# Sheet_4.net
KiCad netlist of a schematic drawn in Altium Designer
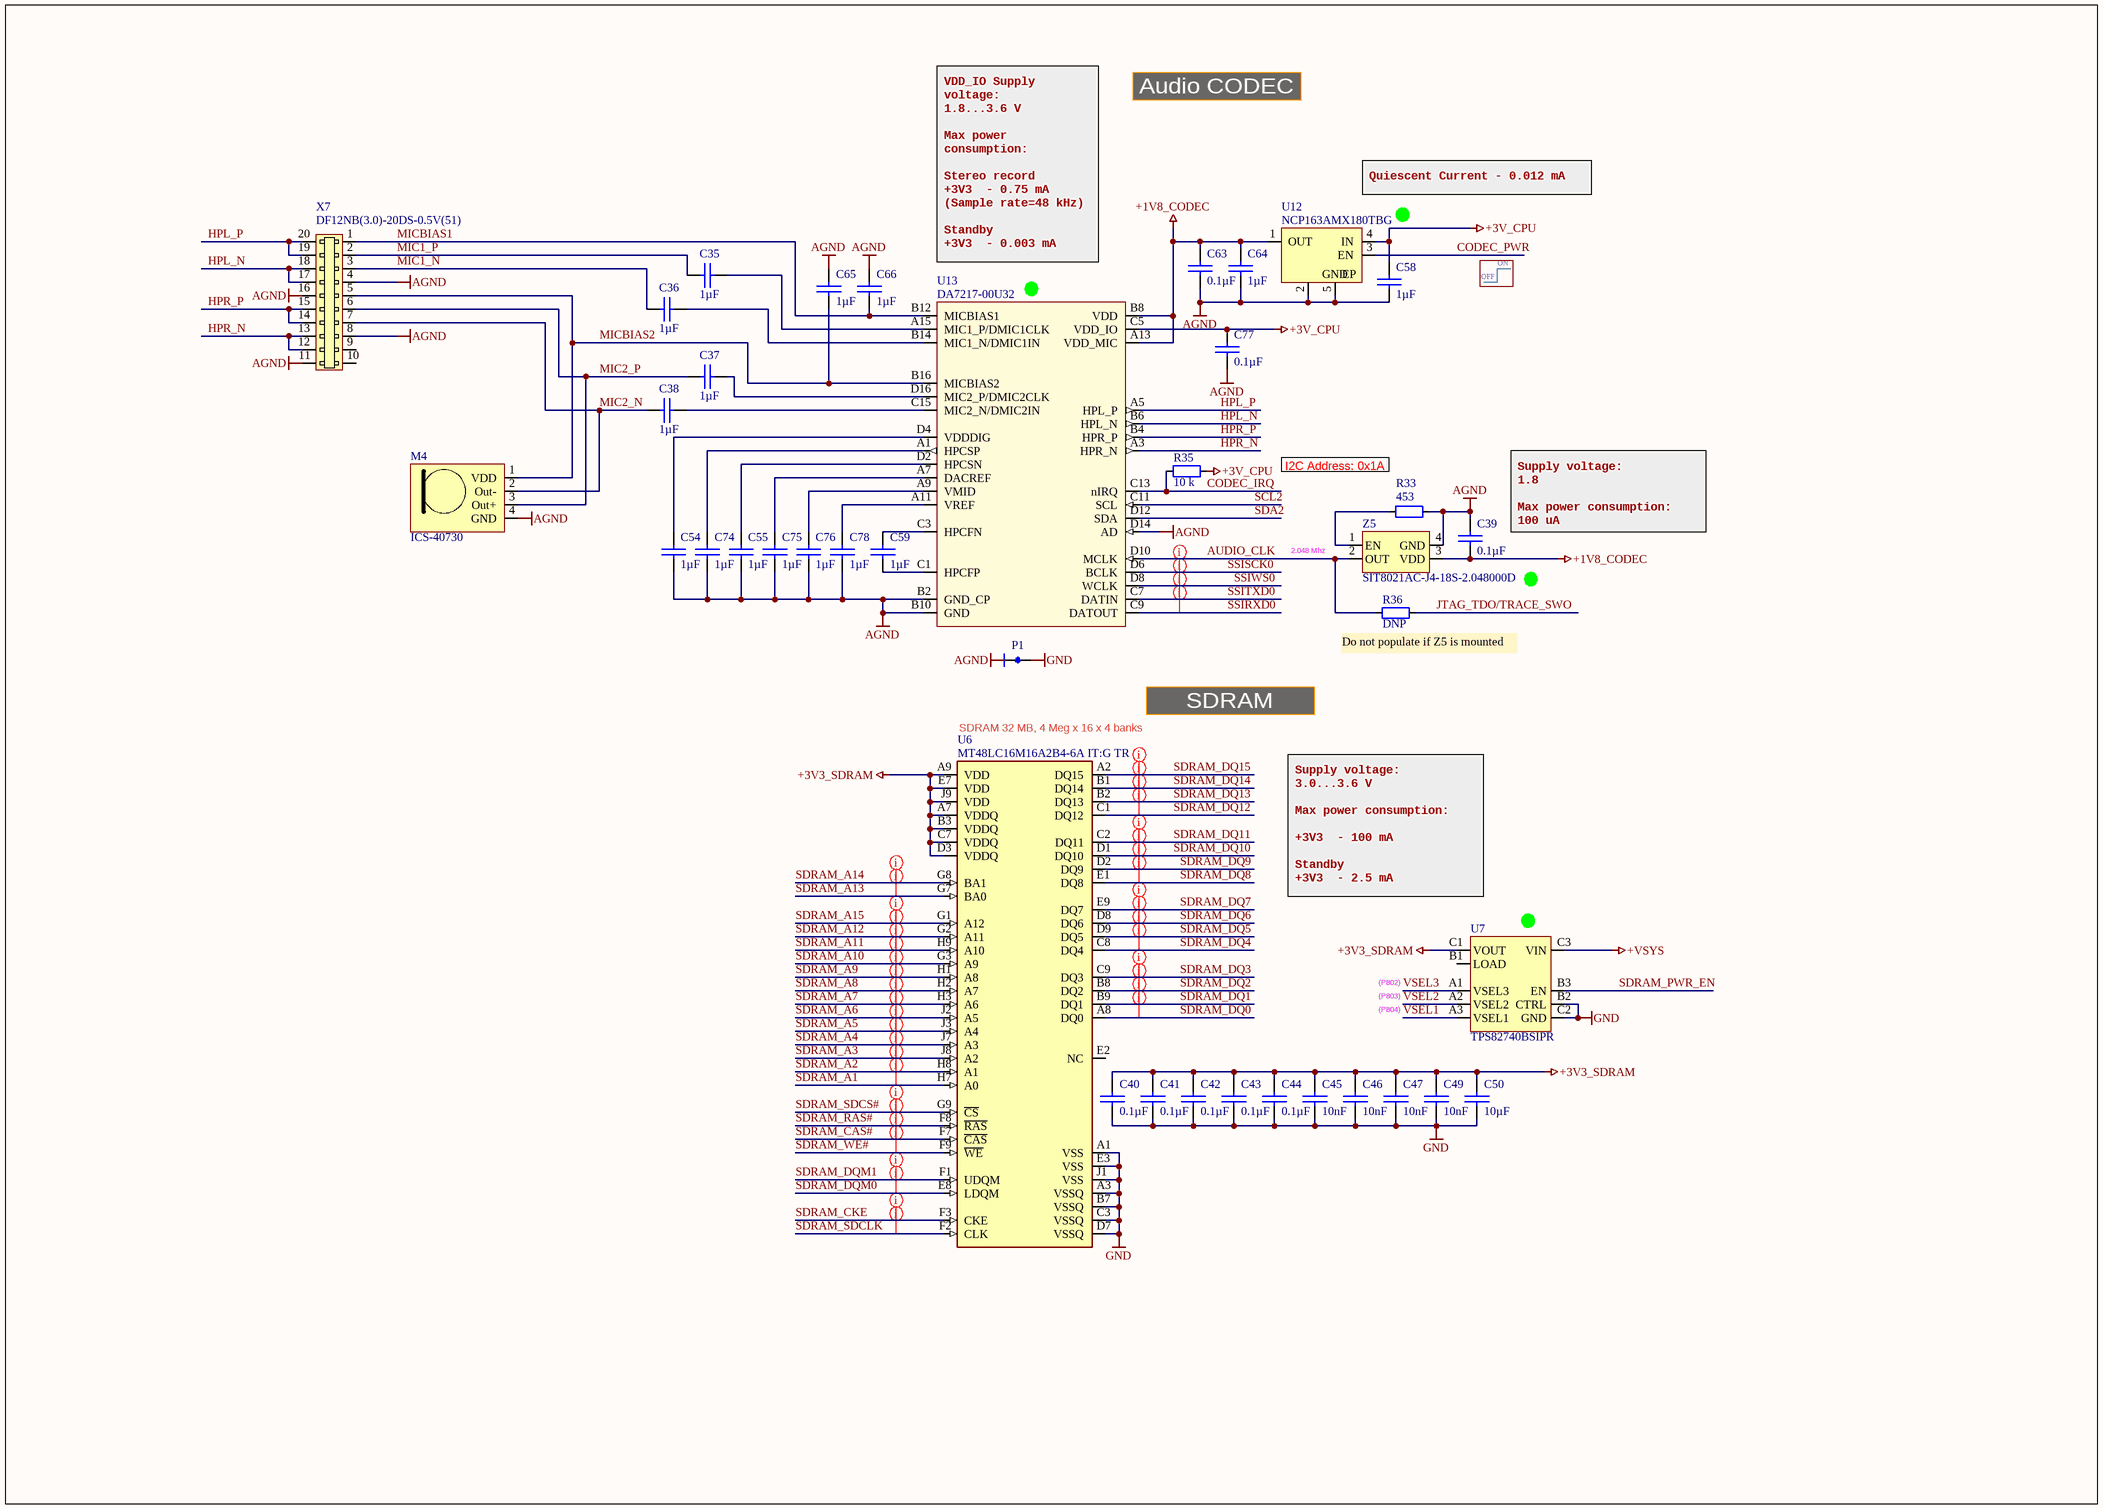
[diagram p0: Sheet_4.SchDoc]

(export (version "E")
  (design (tool "Eeschema 10.0.6"))
  (components
    (comp (ref "C35")
      (value "1µF")
      (footprint "0402 CAP")
      (description "1µF, ±20%, 25V, X5R, 0402 (1005 Metric), -55°C ~ 85°C, -, General Purpose")
      (fields (field (name "PART NUMBER") "TMK105BJ105MV-F") (field (name "MANUFACTURER") "Taiyo Yuden"))
      (libsource (lib "ea_PassivComps") (part "Capacitor"))
    )
    (comp (ref "C36")
      (value "1µF")
      (footprint "0402 CAP")
      (description "1µF, ±20%, 25V, X5R, 0402 (1005 Metric), -55°C ~ 85°C, -, General Purpose")
      (fields (field (name "PART NUMBER") "TMK105BJ105MV-F") (field (name "MANUFACTURER") "Taiyo Yuden"))
      (libsource (lib "ea_PassivComps") (part "Capacitor"))
    )
    (comp (ref "C37")
      (value "1µF")
      (footprint "0402 CAP")
      (description "1µF, ±20%, 25V, X5R, 0402 (1005 Metric), -55°C ~ 85°C, -, General Purpose")
      (fields (field (name "PART NUMBER") "TMK105BJ105MV-F") (field (name "MANUFACTURER") "Taiyo Yuden"))
      (libsource (lib "ea_PassivComps") (part "Capacitor"))
    )
    (comp (ref "C38")
      (value "1µF")
      (footprint "0402 CAP")
      (description "1µF, ±20%, 25V, X5R, 0402 (1005 Metric), -55°C ~ 85°C, -, General Purpose")
      (fields (field (name "PART NUMBER") "TMK105BJ105MV-F") (field (name "MANUFACTURER") "Taiyo Yuden"))
      (libsource (lib "ea_PassivComps") (part "Capacitor"))
    )
    (comp (ref "C39")
      (value "0.1µF")
      (footprint "0402 CAP")
      (description "0.1µF, ±10%, 50V, X7R, 0402 (1005 Metric), -55°C ~ 125°C, -, General Purpose")
      (fields
        (field (name "PART NUMBER") "0402B104K500CT")
        (field (name "MANUFACTURER") "Walsin Technology Corporation")
      )
      (libsource (lib "ea_PassivComps") (part "Capacitor"))
    )
    (comp (ref "C40")
      (value "0.1µF")
      (footprint "0402 CAP")
      (description "0.1µF, ±10%, 50V, X7R, 0402 (1005 Metric), -55°C ~ 125°C, -, General Purpose")
      (fields
        (field (name "PART NUMBER") "0402B104K500CT")
        (field (name "MANUFACTURER") "Walsin Technology Corporation")
      )
      (libsource (lib "ea_PassivComps") (part "Capacitor"))
    )
    (comp (ref "C41")
      (value "0.1µF")
      (footprint "0402 CAP")
      (description "0.1µF, ±10%, 50V, X7R, 0402 (1005 Metric), -55°C ~ 125°C, -, General Purpose")
      (fields
        (field (name "PART NUMBER") "0402B104K500CT")
        (field (name "MANUFACTURER") "Walsin Technology Corporation")
      )
      (libsource (lib "ea_PassivComps") (part "Capacitor"))
    )
    (comp (ref "C42")
      (value "0.1µF")
      (footprint "0402 CAP")
      (description "0.1µF, ±10%, 50V, X7R, 0402 (1005 Metric), -55°C ~ 125°C, -, General Purpose")
      (fields
        (field (name "PART NUMBER") "0402B104K500CT")
        (field (name "MANUFACTURER") "Walsin Technology Corporation")
      )
      (libsource (lib "ea_PassivComps") (part "Capacitor"))
    )
    (comp (ref "C43")
      (value "0.1µF")
      (footprint "0402 CAP")
      (description "0.1µF, ±10%, 50V, X7R, 0402 (1005 Metric), -55°C ~ 125°C, -, General Purpose")
      (fields
        (field (name "PART NUMBER") "0402B104K500CT")
        (field (name "MANUFACTURER") "Walsin Technology Corporation")
      )
      (libsource (lib "ea_PassivComps") (part "Capacitor"))
    )
    (comp (ref "C44")
      (value "0.1µF")
      (footprint "0402 CAP")
      (description "0.1µF, ±10%, 50V, X7R, 0402 (1005 Metric), -55°C ~ 125°C, -, General Purpose")
      (fields
        (field (name "PART NUMBER") "0402B104K500CT")
        (field (name "MANUFACTURER") "Walsin Technology Corporation")
      )
      (libsource (lib "ea_PassivComps") (part "Capacitor"))
    )
    (comp (ref "C45")
      (value "10nF")
      (footprint "0402 CAP")
      (description "10000pF, ±10%, 50V, X7R, 0402 (1005 Metric), -55°C ~ 125°C, -, General Purpose")
      (fields
        (field (name "PART NUMBER") "CL05B103KB5NNNC")
        (field (name "MANUFACTURER") "Samsung Electro-Mechanics")
      )
      (libsource (lib "ea_PassivComps") (part "Capacitor"))
    )
    (comp (ref "C46")
      (value "10nF")
      (footprint "0402 CAP")
      (description "10000pF, ±10%, 50V, X7R, 0402 (1005 Metric), -55°C ~ 125°C, -, General Purpose")
      (fields
        (field (name "PART NUMBER") "CL05B103KB5NNNC")
        (field (name "MANUFACTURER") "Samsung Electro-Mechanics")
      )
      (libsource (lib "ea_PassivComps") (part "Capacitor"))
    )
    (comp (ref "C47")
      (value "10nF")
      (footprint "0402 CAP")
      (description "10000pF, ±10%, 50V, X7R, 0402 (1005 Metric), -55°C ~ 125°C, -, General Purpose")
      (fields
        (field (name "PART NUMBER") "CL05B103KB5NNNC")
        (field (name "MANUFACTURER") "Samsung Electro-Mechanics")
      )
      (libsource (lib "ea_PassivComps") (part "Capacitor"))
    )
    (comp (ref "C49")
      (value "10nF")
      (footprint "0402 CAP")
      (description "10000pF, ±10%, 50V, X7R, 0402 (1005 Metric), -55°C ~ 125°C, -, General Purpose")
      (fields
        (field (name "PART NUMBER") "CL05B103KB5NNNC")
        (field (name "MANUFACTURER") "Samsung Electro-Mechanics")
      )
      (libsource (lib "ea_PassivComps") (part "Capacitor"))
    )
    (comp (ref "C50")
      (value "10µF")
      (footprint "0603 CAP")
      (description "10µF, ±10%, 16V, X5R, 0603 (1608 Metric), -55°C ~ 85°C, -, Automotive")
      (fields
        (field (name "PART NUMBER") "GRT188R61C106KE13D")
        (field (name "MANUFACTURER") "Murata Electronics North America")
      )
      (libsource (lib "ea_PassivComps") (part "Capacitor"))
    )
    (comp (ref "C54")
      (value "1µF")
      (footprint "0402 CAP")
      (description "1µF, ±20%, 25V, X5R, 0402 (1005 Metric), -55°C ~ 85°C, -, General Purpose")
      (fields (field (name "PART NUMBER") "TMK105BJ105MV-F") (field (name "MANUFACTURER") "Taiyo Yuden"))
      (libsource (lib "ea_PassivComps") (part "Capacitor"))
    )
    (comp (ref "C55")
      (value "1µF")
      (footprint "0402 CAP")
      (description "1µF, ±20%, 25V, X5R, 0402 (1005 Metric), -55°C ~ 85°C, -, General Purpose")
      (fields (field (name "PART NUMBER") "TMK105BJ105MV-F") (field (name "MANUFACTURER") "Taiyo Yuden"))
      (libsource (lib "ea_PassivComps") (part "Capacitor"))
    )
    (comp (ref "C58")
      (value "1µF")
      (footprint "0402 CAP")
      (description "1µF, ±20%, 25V, X5R, 0402 (1005 Metric), -55°C ~ 85°C, -, General Purpose")
      (fields (field (name "PART NUMBER") "TMK105BJ105MV-F") (field (name "MANUFACTURER") "Taiyo Yuden"))
      (libsource (lib "ea_PassivComps") (part "Capacitor"))
    )
    (comp (ref "C59")
      (value "1µF")
      (footprint "0402 CAP")
      (description "1µF, ±20%, 25V, X5R, 0402 (1005 Metric), -55°C ~ 85°C, -, General Purpose")
      (fields (field (name "PART NUMBER") "TMK105BJ105MV-F") (field (name "MANUFACTURER") "Taiyo Yuden"))
      (libsource (lib "ea_PassivComps") (part "Capacitor"))
    )
    (comp (ref "C63")
      (value "0.1µF")
      (footprint "0402 CAP")
      (description "0.1µF, ±10%, 50V, X7R, 0402 (1005 Metric), -55°C ~ 125°C, -, General Purpose")
      (fields
        (field (name "PART NUMBER") "0402B104K500CT")
        (field (name "MANUFACTURER") "Walsin Technology Corporation")
      )
      (libsource (lib "ea_PassivComps") (part "Capacitor"))
    )
    (comp (ref "C64")
      (value "1µF")
      (footprint "0402 CAP")
      (description "1µF, ±20%, 25V, X5R, 0402 (1005 Metric), -55°C ~ 85°C, -, General Purpose")
      (fields (field (name "PART NUMBER") "TMK105BJ105MV-F") (field (name "MANUFACTURER") "Taiyo Yuden"))
      (libsource (lib "ea_PassivComps") (part "Capacitor"))
    )
    (comp (ref "C65")
      (value "1µF")
      (footprint "0402 CAP")
      (description "1µF, ±20%, 25V, X5R, 0402 (1005 Metric), -55°C ~ 85°C, -, General Purpose")
      (fields (field (name "PART NUMBER") "TMK105BJ105MV-F") (field (name "MANUFACTURER") "Taiyo Yuden"))
      (libsource (lib "ea_PassivComps") (part "Capacitor"))
    )
    (comp (ref "C66")
      (value "1µF")
      (footprint "0402 CAP")
      (description "1µF, ±20%, 25V, X5R, 0402 (1005 Metric), -55°C ~ 85°C, -, General Purpose")
      (fields (field (name "PART NUMBER") "TMK105BJ105MV-F") (field (name "MANUFACTURER") "Taiyo Yuden"))
      (libsource (lib "ea_PassivComps") (part "Capacitor"))
    )
    (comp (ref "C74")
      (value "1µF")
      (footprint "0402 CAP")
      (description "1µF, ±20%, 25V, X5R, 0402 (1005 Metric), -55°C ~ 85°C, -, General Purpose")
      (fields (field (name "PART NUMBER") "TMK105BJ105MV-F") (field (name "MANUFACTURER") "Taiyo Yuden"))
      (libsource (lib "ea_PassivComps") (part "Capacitor"))
    )
    (comp (ref "C75")
      (value "1µF")
      (footprint "0402 CAP")
      (description "1µF, ±20%, 25V, X5R, 0402 (1005 Metric), -55°C ~ 85°C, -, General Purpose")
      (fields (field (name "PART NUMBER") "TMK105BJ105MV-F") (field (name "MANUFACTURER") "Taiyo Yuden"))
      (libsource (lib "ea_PassivComps") (part "Capacitor"))
    )
    (comp (ref "C76")
      (value "1µF")
      (footprint "0402 CAP")
      (description "1µF, ±20%, 25V, X5R, 0402 (1005 Metric), -55°C ~ 85°C, -, General Purpose")
      (fields (field (name "PART NUMBER") "TMK105BJ105MV-F") (field (name "MANUFACTURER") "Taiyo Yuden"))
      (libsource (lib "ea_PassivComps") (part "Capacitor"))
    )
    (comp (ref "C77")
      (value "0.1µF")
      (footprint "0402 CAP")
      (description "0.1µF, ±10%, 50V, X7R, 0402 (1005 Metric), -55°C ~ 125°C, -, General Purpose")
      (fields
        (field (name "PART NUMBER") "0402B104K500CT")
        (field (name "MANUFACTURER") "Walsin Technology Corporation")
      )
      (libsource (lib "ea_PassivComps") (part "Capacitor"))
    )
    (comp (ref "C78")
      (value "1µF")
      (footprint "0402 CAP")
      (description "1µF, ±20%, 25V, X5R, 0402 (1005 Metric), -55°C ~ 85°C, -, General Purpose")
      (fields (field (name "PART NUMBER") "TMK105BJ105MV-F") (field (name "MANUFACTURER") "Taiyo Yuden"))
      (libsource (lib "ea_PassivComps") (part "Capacitor"))
    )
    (comp (ref "M4")
      (value "ICS-40730")
      (footprint "ICS-40730")
      (fields (field (name "MANUFACTURER") "TDK InvenSense") (field (name "PARTNUM") "1428-1141-1-ND"))
      (libsource (lib "ea_Sound_devices") (part "ICS-40730"))
    )
    (comp (ref "P1")
      (value "Net tie 0.1mm")
      (footprint "Net tee 0.1 mm")
      (libsource (lib "ea_Mechanical") (part "Net tie 0.1mm"))
    )
    (comp (ref "R33")
      (value "453")
      (footprint "0402")
      (fields
        (field (name "MANUFACTURER") "Stackpole Electronics Inc")
        (field (name "TOLERANCE") "±1%")
        (field (name "VOLTAGE") "75V")
      )
      (libsource (lib "ea_PassivComps") (part "Resistor"))
    )
    (comp (ref "R35")
      (value "10 k")
      (footprint "0402")
      (fields
        (field (name "MANUFACTURER") "Stackpole Electronics Inc")
        (field (name "TOLERANCE") "±1%")
        (field (name "VOLTAGE") "75V")
      )
      (libsource (lib "") (part "Resistor_1"))
    )
    (comp (ref "R36")
      (value "DNP")
      (footprint "0402")
      (fields (field (name "Comment") "Resistor"))
      (libsource (lib "ea_PassivComps") (part "Resistor"))
    )
    (comp (ref "U6")
      (value "MT48LC16M16A2B4-6A IT:G TR")
      (footprint "MICRON_VFBGA54")
      (description "Micron SDRAM 256M-Bit 16Mx16, 3.3V, 167MHz, 6ns, -40°C ~ +85°C, 54-VFBGA (8x8) Pb-free")
      (fields
        (field (name "MANUFACTURER") "Micron Technology Inc.")
        (field (name "PARTNUM") "340-128306-REEL")
      )
      (libsource (lib "ea_IC_RAM") (part "MT48LC16M16A2B4-6A IT{colon}G TR"))
    )
    (comp (ref "U7")
      (value "TPS82740BSIPR")
      (footprint "MicroSiP")
      (fields (field (name "MANUFACTURER") "Texas Instruments") (field (name "PARTNUM") "296-46481-1-ND"))
      (libsource (lib "ea_IC_Power_Reg_Ref_Sw") (part "TPS82740BSIPR"))
    )
    (comp (ref "U12")
      (value "NCP163AMX180TBG")
      (footprint "4-XDFN")
      (description "LDO 1.8V, 250 mA, Vin < 5.5V, Iq < 20uA, -40..+125 C,  4-XDFN (1x1)")
      (fields
        (field (name "MANUFACTURER") "ON Semiconductor")
        (field (name "PARTNUM") "NCP163AMX180TBGOSCT-ND")
      )
      (libsource (lib "ea_IC_Linear_reg_LDO") (part "NCP163AMX180TBG"))
    )
    (comp (ref "U13")
      (value "DA7217-00U32")
      (footprint "Dilaog 34-WLCSP (4.57x1.98)")
      (description "Low power CODEC, 24 b, 2/2, I²C, I²S,  1.5V ~ 3.6V,  -25°C ~ 85°C, 34-WLCSP (4.57x1.98)")
      (fields
        (field (name "MANUFACTURER") "Dialog Semiconductor GmbH")
        (field (name "PARTNUM") "1564-1043-1-ND")
      )
      (libsource (lib "ea_IC_audio") (part "DA7217-00U32"))
    )
    (comp (ref "X7")
      (value "DF12NB(3.0)-20DS-0.5V(51)")
      (footprint "DF12NB(3.0)-20DS-0.5V(51)")
      (fields
        (field (name "MANUFACTURER") "Hirose Electric")
        (field (name "PARTNUM") "26-DF12NB(3.0)-20DS-0.5V(51)CT-ND - Cut Tape (CT)")
      )
      (libsource (lib "ea_Connectors_0.5_mm_pitch") (part "DF12NB(3.0)-20DS-0.5V(51)"))
    )
    (comp (ref "Z5")
      (value "SIT8021AC-J4-18S-2.048000D")
      (footprint "SiT8021")
      (description "2.048MHz XO (Standard) LVCMOS Oscillator 1.8V Standby (Power Down) 4-UFBGA, CSPBGA, -20...+70 C")
      (fields (field (name "MANUFACTURER") "SiTIME"))
      (libsource (lib "ea_OSC_CLK_GEN") (part "SIT8021AC-J4-18S-2.048000D"))
    )
  )
  (nets
    (net (code "1") (name "+1V8_CODEC") (class "Default")
      (node (ref "C39") (pin "2") (pinfunction "2_2") (pintype "passive"))
      (node (ref "C63") (pin "1") (pinfunction "1_1") (pintype "passive"))
      (node (ref "C64") (pin "1") (pinfunction "1_1") (pintype "passive"))
      (node (ref "U12") (pin "1") (pinfunction "OUT_1") (pintype "power_in"))
      (node (ref "U13") (pin "A13") (pinfunction "VDD_MIC_A13") (pintype "power_in"))
      (node (ref "U13") (pin "B8") (pinfunction "VDD_B8") (pintype "power_in"))
      (node (ref "Z5") (pin "3") (pinfunction "VDD_3") (pintype "passive"))
    )
    (net (code "2") (name "+3V3_SDRAM") (class "Default")
      (node (ref "C40") (pin "1") (pinfunction "1_1") (pintype "passive"))
      (node (ref "C41") (pin "1") (pinfunction "1_1") (pintype "passive"))
      (node (ref "C42") (pin "1") (pinfunction "1_1") (pintype "passive"))
      (node (ref "C43") (pin "1") (pinfunction "1_1") (pintype "passive"))
      (node (ref "C44") (pin "1") (pinfunction "1_1") (pintype "passive"))
      (node (ref "C45") (pin "1") (pinfunction "1_1") (pintype "passive"))
      (node (ref "C46") (pin "1") (pinfunction "1_1") (pintype "passive"))
      (node (ref "C47") (pin "1") (pinfunction "1_1") (pintype "passive"))
      (node (ref "C49") (pin "1") (pinfunction "1_1") (pintype "passive"))
      (node (ref "C50") (pin "1") (pinfunction "1_1") (pintype "passive"))
      (node (ref "U6") (pin "A7") (pinfunction "VDDQ_A7") (pintype "power_in"))
      (node (ref "U6") (pin "A9") (pinfunction "VDD_A9") (pintype "power_in"))
      (node (ref "U6") (pin "B3") (pinfunction "VDDQ_B3") (pintype "power_in"))
      (node (ref "U6") (pin "C7") (pinfunction "VDDQ_C7") (pintype "power_in"))
      (node (ref "U6") (pin "D3") (pinfunction "VDDQ_D3") (pintype "power_in"))
      (node (ref "U6") (pin "E7") (pinfunction "VDD_E7") (pintype "power_in"))
      (node (ref "U6") (pin "J9") (pinfunction "VDD_J9") (pintype "power_in"))
      (node (ref "U7") (pin "C1") (pinfunction "VOUT_C1") (pintype "passive"))
    )
    (net (code "3") (name "+3V_CPU") (class "Default")
      (node (ref "C58") (pin "1") (pinfunction "1_1") (pintype "passive"))
      (node (ref "C77") (pin "1") (pinfunction "1_1") (pintype "passive"))
      (node (ref "R35") (pin "2") (pinfunction "2_2") (pintype "passive"))
      (node (ref "U12") (pin "4") (pinfunction "IN_4") (pintype "power_in"))
      (node (ref "U13") (pin "C5") (pinfunction "VDD_IO_C5") (pintype "power_in"))
    )
    (net (code "4") (name "+VSYS") (class "Default")
      (node (ref "U7") (pin "C3") (pinfunction "VIN_C3") (pintype "passive"))
    )
    (net (code "5") (name "/AUDIO_CLK") (class "Default")
      (node (ref "R36") (pin "2") (pinfunction "2_2") (pintype "passive"))
      (node (ref "U13") (pin "D10") (pinfunction "MCLK_D10") (pintype "input"))
      (node (ref "Z5") (pin "2") (pinfunction "OUT_2") (pintype "passive"))
    )
    (net (code "6") (name "/CODEC_IRQ") (class "Default")
      (node (ref "R35") (pin "1") (pinfunction "1_1") (pintype "passive"))
      (node (ref "U13") (pin "C13") (pinfunction "nIRQ_C13") (pintype "bidirectional"))
    )
    (net (code "7") (name "/CODEC_PWR") (class "Default")
      (node (ref "U12") (pin "3") (pinfunction "EN_3") (pintype "power_in"))
    )
    (net (code "8") (name "/HPL_N") (class "Default")
      (node (ref "U13") (pin "B6") (pinfunction "HPL_N_B6") (pintype "output"))
      (node (ref "X7") (pin "17") (pinfunction "9_17") (pintype "passive"))
      (node (ref "X7") (pin "18") (pinfunction "10_18") (pintype "passive"))
    )
    (net (code "9") (name "/HPL_P") (class "Default")
      (node (ref "U13") (pin "A5") (pinfunction "HPL_P_A5") (pintype "output"))
      (node (ref "X7") (pin "19") (pinfunction "10_19") (pintype "passive"))
      (node (ref "X7") (pin "20") (pinfunction "11_20") (pintype "passive"))
    )
    (net (code "10") (name "/HPR_N") (class "Default")
      (node (ref "U13") (pin "A3") (pinfunction "HPR_N_A3") (pintype "output"))
      (node (ref "X7") (pin "12") (pinfunction "7_12") (pintype "passive"))
      (node (ref "X7") (pin "13") (pinfunction "7_13") (pintype "passive"))
    )
    (net (code "11") (name "/HPR_P") (class "Default")
      (node (ref "U13") (pin "B4") (pinfunction "HPR_P_B4") (pintype "output"))
      (node (ref "X7") (pin "14") (pinfunction "8_14") (pintype "passive"))
      (node (ref "X7") (pin "15") (pinfunction "8_15") (pintype "passive"))
    )
    (net (code "12") (name "/JTAG_TDO{slash}TRACE_SWO") (class "Default")
      (node (ref "R36") (pin "1") (pinfunction "1_1") (pintype "passive"))
    )
    (net (code "13") (name "/MIC1_N") (class "Default")
      (node (ref "C36") (pin "1") (pinfunction "1_1") (pintype "passive"))
      (node (ref "X7") (pin "3") (pinfunction "2_3") (pintype "passive"))
    )
    (net (code "14") (name "/MIC1_P") (class "Default")
      (node (ref "C35") (pin "1") (pinfunction "1_1") (pintype "passive"))
      (node (ref "X7") (pin "2") (pinfunction "2_2") (pintype "passive"))
    )
    (net (code "15") (name "/MIC2_N") (class "Default")
      (node (ref "C38") (pin "1") (pinfunction "1_1") (pintype "passive"))
      (node (ref "M4") (pin "2") (pinfunction "Out-_2") (pintype "passive"))
      (node (ref "X7") (pin "7") (pinfunction "4_7") (pintype "passive"))
    )
    (net (code "16") (name "/MIC2_P") (class "Default")
      (node (ref "C37") (pin "1") (pinfunction "1_1") (pintype "passive"))
      (node (ref "M4") (pin "3") (pinfunction "Out+_3") (pintype "passive"))
      (node (ref "X7") (pin "6") (pinfunction "4_6") (pintype "passive"))
    )
    (net (code "17") (name "/MICBIAS1") (class "Default")
      (node (ref "C66") (pin "2") (pinfunction "2_2") (pintype "passive"))
      (node (ref "U13") (pin "B12") (pinfunction "MICBIAS1_B12") (pintype "bidirectional"))
      (node (ref "X7") (pin "1") (pinfunction "1_1") (pintype "passive"))
    )
    (net (code "18") (name "/MICBIAS2") (class "Default")
      (node (ref "C65") (pin "2") (pinfunction "2_2") (pintype "passive"))
      (node (ref "M4") (pin "1") (pinfunction "VDD_1") (pintype "passive"))
      (node (ref "U13") (pin "B16") (pinfunction "MICBIAS2_B16") (pintype "bidirectional"))
      (node (ref "X7") (pin "5") (pinfunction "3_5") (pintype "passive"))
    )
    (net (code "19") (name "/SCL2") (class "Default")
      (node (ref "U13") (pin "C11") (pinfunction "SCL_C11") (pintype "input"))
    )
    (net (code "20") (name "/SDA2") (class "Default")
      (node (ref "U13") (pin "D12") (pinfunction "SDA_D12") (pintype "bidirectional"))
    )
    (net (code "21") (name "/SDRAM_A1") (class "Default")
      (node (ref "U6") (pin "H7") (pinfunction "A0_H7") (pintype "input"))
    )
    (net (code "22") (name "/SDRAM_A2") (class "Default")
      (node (ref "U6") (pin "H8") (pinfunction "A1_H8") (pintype "input"))
    )
    (net (code "23") (name "/SDRAM_A3") (class "Default")
      (node (ref "U6") (pin "J8") (pinfunction "A2_J8") (pintype "input"))
    )
    (net (code "24") (name "/SDRAM_A4") (class "Default")
      (node (ref "U6") (pin "J7") (pinfunction "A3_J7") (pintype "input"))
    )
    (net (code "25") (name "/SDRAM_A5") (class "Default")
      (node (ref "U6") (pin "J3") (pinfunction "A4_J3") (pintype "input"))
    )
    (net (code "26") (name "/SDRAM_A6") (class "Default")
      (node (ref "U6") (pin "J2") (pinfunction "A5_J2") (pintype "input"))
    )
    (net (code "27") (name "/SDRAM_A7") (class "Default")
      (node (ref "U6") (pin "H3") (pinfunction "A6_H3") (pintype "input"))
    )
    (net (code "28") (name "/SDRAM_A8") (class "Default")
      (node (ref "U6") (pin "H2") (pinfunction "A7_H2") (pintype "input"))
    )
    (net (code "29") (name "/SDRAM_A9") (class "Default")
      (node (ref "U6") (pin "H1") (pinfunction "A8_H1") (pintype "input"))
    )
    (net (code "30") (name "/SDRAM_A10") (class "Default")
      (node (ref "U6") (pin "G3") (pinfunction "A9_G3") (pintype "input"))
    )
    (net (code "31") (name "/SDRAM_A11") (class "Default")
      (node (ref "U6") (pin "H9") (pinfunction "A10_H9") (pintype "input"))
    )
    (net (code "32") (name "/SDRAM_A12") (class "Default")
      (node (ref "U6") (pin "G2") (pinfunction "A11_G2") (pintype "input"))
    )
    (net (code "33") (name "/SDRAM_A13") (class "Default")
      (node (ref "U6") (pin "G7") (pinfunction "BA0_G7") (pintype "input"))
    )
    (net (code "34") (name "/SDRAM_A14") (class "Default")
      (node (ref "U6") (pin "G8") (pinfunction "BA1_G8") (pintype "input"))
    )
    (net (code "35") (name "/SDRAM_A15") (class "Default")
      (node (ref "U6") (pin "G1") (pinfunction "A12_G1") (pintype "input"))
    )
    (net (code "36") (name "/SDRAM_CAS#") (class "Default")
      (node (ref "U6") (pin "F7") (pinfunction "~{CAS}_F7") (pintype "input"))
    )
    (net (code "37") (name "/SDRAM_CKE") (class "Default")
      (node (ref "U6") (pin "F3") (pinfunction "CKE_F3") (pintype "input"))
    )
    (net (code "38") (name "/SDRAM_DQ0") (class "Default")
      (node (ref "U6") (pin "A8") (pinfunction "DQ0_A8") (pintype "bidirectional"))
    )
    (net (code "39") (name "/SDRAM_DQ1") (class "Default")
      (node (ref "U6") (pin "B9") (pinfunction "DQ1_B9") (pintype "bidirectional"))
    )
    (net (code "40") (name "/SDRAM_DQ2") (class "Default")
      (node (ref "U6") (pin "B8") (pinfunction "DQ2_B8") (pintype "bidirectional"))
    )
    (net (code "41") (name "/SDRAM_DQ3") (class "Default")
      (node (ref "U6") (pin "C9") (pinfunction "DQ3_C9") (pintype "bidirectional"))
    )
    (net (code "42") (name "/SDRAM_DQ4") (class "Default")
      (node (ref "U6") (pin "C8") (pinfunction "DQ4_C8") (pintype "bidirectional"))
    )
    (net (code "43") (name "/SDRAM_DQ5") (class "Default")
      (node (ref "U6") (pin "D9") (pinfunction "DQ5_D9") (pintype "bidirectional"))
    )
    (net (code "44") (name "/SDRAM_DQ6") (class "Default")
      (node (ref "U6") (pin "D8") (pinfunction "DQ6_D8") (pintype "bidirectional"))
    )
    (net (code "45") (name "/SDRAM_DQ7") (class "Default")
      (node (ref "U6") (pin "E9") (pinfunction "DQ7_E9") (pintype "bidirectional"))
    )
    (net (code "46") (name "/SDRAM_DQ8") (class "Default")
      (node (ref "U6") (pin "E1") (pinfunction "DQ8_E1") (pintype "bidirectional"))
    )
    (net (code "47") (name "/SDRAM_DQ9") (class "Default")
      (node (ref "U6") (pin "D2") (pinfunction "DQ9_D2") (pintype "bidirectional"))
    )
    (net (code "48") (name "/SDRAM_DQ10") (class "Default")
      (node (ref "U6") (pin "D1") (pinfunction "DQ10_D1") (pintype "bidirectional"))
    )
    (net (code "49") (name "/SDRAM_DQ11") (class "Default")
      (node (ref "U6") (pin "C2") (pinfunction "DQ11_C2") (pintype "bidirectional"))
    )
    (net (code "50") (name "/SDRAM_DQ12") (class "Default")
      (node (ref "U6") (pin "C1") (pinfunction "DQ12_C1") (pintype "bidirectional"))
    )
    (net (code "51") (name "/SDRAM_DQ13") (class "Default")
      (node (ref "U6") (pin "B2") (pinfunction "DQ13_B2") (pintype "bidirectional"))
    )
    (net (code "52") (name "/SDRAM_DQ14") (class "Default")
      (node (ref "U6") (pin "B1") (pinfunction "DQ14_B1") (pintype "bidirectional"))
    )
    (net (code "53") (name "/SDRAM_DQ15") (class "Default")
      (node (ref "U6") (pin "A2") (pinfunction "DQ15_A2") (pintype "bidirectional"))
    )
    (net (code "54") (name "/SDRAM_DQM0") (class "Default")
      (node (ref "U6") (pin "E8") (pinfunction "LDQM_E8") (pintype "input"))
    )
    (net (code "55") (name "/SDRAM_DQM1") (class "Default")
      (node (ref "U6") (pin "F1") (pinfunction "UDQM_F1") (pintype "input"))
    )
    (net (code "56") (name "/SDRAM_PWR_EN") (class "Default")
      (node (ref "U7") (pin "B3") (pinfunction "EN_B3") (pintype "passive"))
    )
    (net (code "57") (name "/SDRAM_RAS#") (class "Default")
      (node (ref "U6") (pin "F8") (pinfunction "~{RAS}_F8") (pintype "input"))
    )
    (net (code "58") (name "/SDRAM_SDCLK") (class "Default")
      (node (ref "U6") (pin "F2") (pinfunction "CLK_F2") (pintype "input"))
    )
    (net (code "59") (name "/SDRAM_SDCS#") (class "Default")
      (node (ref "U6") (pin "G9") (pinfunction "~{CS}_G9") (pintype "input"))
    )
    (net (code "60") (name "/SDRAM_WE#") (class "Default")
      (node (ref "U6") (pin "F9") (pinfunction "~{WE}_F9") (pintype "input"))
    )
    (net (code "61") (name "/SSIRXD0") (class "Default")
      (node (ref "U13") (pin "C9") (pinfunction "DATOUT_C9") (pintype "bidirectional"))
    )
    (net (code "62") (name "/SSISCK0") (class "Default")
      (node (ref "U13") (pin "D6") (pinfunction "BCLK_D6") (pintype "bidirectional"))
    )
    (net (code "63") (name "/SSITXD0") (class "Default")
      (node (ref "U13") (pin "C7") (pinfunction "DATIN_C7") (pintype "bidirectional"))
    )
    (net (code "64") (name "/SSIWS0") (class "Default")
      (node (ref "U13") (pin "D8") (pinfunction "WCLK_D8") (pintype "bidirectional"))
    )
    (net (code "65") (name "/VSEL1") (class "Default")
      (node (ref "U7") (pin "A3") (pinfunction "VSEL1_A3") (pintype "passive"))
    )
    (net (code "66") (name "/VSEL2") (class "Default")
      (node (ref "U7") (pin "A2") (pinfunction "VSEL2_A2") (pintype "passive"))
    )
    (net (code "67") (name "/VSEL3") (class "Default")
      (node (ref "U7") (pin "A1") (pinfunction "VSEL3_A1") (pintype "passive"))
    )
    (net (code "68") (name "AGND") (class "Default")
      (node (ref "C39") (pin "1") (pinfunction "1_1") (pintype "passive"))
      (node (ref "C54") (pin "2") (pinfunction "2_2") (pintype "passive"))
      (node (ref "C55") (pin "2") (pinfunction "2_2") (pintype "passive"))
      (node (ref "C58") (pin "2") (pinfunction "2_2") (pintype "passive"))
      (node (ref "C63") (pin "2") (pinfunction "2_2") (pintype "passive"))
      (node (ref "C64") (pin "2") (pinfunction "2_2") (pintype "passive"))
      (node (ref "C65") (pin "1") (pinfunction "1_1") (pintype "passive"))
      (node (ref "C66") (pin "1") (pinfunction "1_1") (pintype "passive"))
      (node (ref "C74") (pin "2") (pinfunction "2_2") (pintype "passive"))
      (node (ref "C75") (pin "2") (pinfunction "2_2") (pintype "passive"))
      (node (ref "C76") (pin "2") (pinfunction "2_2") (pintype "passive"))
      (node (ref "C77") (pin "2") (pinfunction "2_2") (pintype "passive"))
      (node (ref "C78") (pin "2") (pinfunction "2_2") (pintype "passive"))
      (node (ref "M4") (pin "4") (pinfunction "GND_4") (pintype "passive"))
      (node (ref "P1") (pin "1") (pinfunction "1_1") (pintype "passive"))
      (node (ref "R33") (pin "1") (pinfunction "1_1") (pintype "passive"))
      (node (ref "U12") (pin "2") (pinfunction "GND_2") (pintype "power_in"))
      (node (ref "U12") (pin "5") (pinfunction "EP_5") (pintype "power_in"))
      (node (ref "U13") (pin "B10") (pinfunction "GND_B10") (pintype "power_in"))
      (node (ref "U13") (pin "B2") (pinfunction "GND_CP_B2") (pintype "power_in"))
      (node (ref "U13") (pin "D14") (pinfunction "AD_D14") (pintype "input"))
      (node (ref "X7") (pin "11") (pinfunction "6_11") (pintype "passive"))
      (node (ref "X7") (pin "16") (pinfunction "9_16") (pintype "passive"))
      (node (ref "X7") (pin "4") (pinfunction "3_4") (pintype "passive"))
      (node (ref "X7") (pin "8") (pinfunction "5_8") (pintype "passive"))
      (node (ref "Z5") (pin "4") (pinfunction "GND_4") (pintype "passive"))
    )
    (net (code "69") (name "GND") (class "Default")
      (node (ref "C40") (pin "2") (pinfunction "2_2") (pintype "passive"))
      (node (ref "C41") (pin "2") (pinfunction "2_2") (pintype "passive"))
      (node (ref "C42") (pin "2") (pinfunction "2_2") (pintype "passive"))
      (node (ref "C43") (pin "2") (pinfunction "2_2") (pintype "passive"))
      (node (ref "C44") (pin "2") (pinfunction "2_2") (pintype "passive"))
      (node (ref "C45") (pin "2") (pinfunction "2_2") (pintype "passive"))
      (node (ref "C46") (pin "2") (pinfunction "2_2") (pintype "passive"))
      (node (ref "C47") (pin "2") (pinfunction "2_2") (pintype "passive"))
      (node (ref "C49") (pin "2") (pinfunction "2_2") (pintype "passive"))
      (node (ref "C50") (pin "2") (pinfunction "2_2") (pintype "passive"))
      (node (ref "P1") (pin "2") (pinfunction "2_2") (pintype "passive"))
      (node (ref "U6") (pin "A1") (pinfunction "VSS_A1") (pintype "power_in"))
      (node (ref "U6") (pin "A3") (pinfunction "VSSQ_A3") (pintype "power_in"))
      (node (ref "U6") (pin "B7") (pinfunction "VSSQ_B7") (pintype "power_in"))
      (node (ref "U6") (pin "C3") (pinfunction "VSSQ_C3") (pintype "power_in"))
      (node (ref "U6") (pin "D7") (pinfunction "VSSQ_D7") (pintype "power_in"))
      (node (ref "U6") (pin "E3") (pinfunction "VSS_E3") (pintype "power_in"))
      (node (ref "U6") (pin "J1") (pinfunction "VSS_J1") (pintype "power_in"))
      (node (ref "U7") (pin "B2") (pinfunction "CTRL_B2") (pintype "passive"))
      (node (ref "U7") (pin "C2") (pinfunction "GND_C2") (pintype "passive"))
    )
    (net (code "70") (name "Net-(U13-DACREF)") (class "Default")
      (node (ref "C75") (pin "1") (pinfunction "1_1") (pintype "passive"))
      (node (ref "U13") (pin "A7") (pinfunction "DACREF_A7") (pintype "power_in"))
    )
    (net (code "71") (name "Net-(U13-HPCFN)") (class "Default")
      (node (ref "C59") (pin "1") (pinfunction "1_1") (pintype "passive"))
      (node (ref "U13") (pin "C3") (pinfunction "HPCFN_C3") (pintype "bidirectional"))
    )
    (net (code "72") (name "Net-(U13-HPCFP)") (class "Default")
      (node (ref "C59") (pin "2") (pinfunction "2_2") (pintype "passive"))
      (node (ref "U13") (pin "C1") (pinfunction "HPCFP_C1") (pintype "bidirectional"))
    )
    (net (code "73") (name "Net-(U13-HPCSN)") (class "Default")
      (node (ref "C55") (pin "1") (pinfunction "1_1") (pintype "passive"))
      (node (ref "U13") (pin "D2") (pinfunction "HPCSN_D2") (pintype "bidirectional"))
    )
    (net (code "74") (name "Net-(U13-HPCSP)") (class "Default")
      (node (ref "C74") (pin "1") (pinfunction "1_1") (pintype "passive"))
      (node (ref "U13") (pin "A1") (pinfunction "HPCSP_A1") (pintype "output"))
    )
    (net (code "75") (name "Net-(U13-MIC1_N{slash}DMIC1IN)") (class "Default")
      (node (ref "C36") (pin "2") (pinfunction "2_2") (pintype "passive"))
      (node (ref "U13") (pin "B14") (pinfunction "MIC1_N/DMIC1IN_B14") (pintype "bidirectional"))
    )
    (net (code "76") (name "Net-(U13-MIC1_P{slash}DMIC1CLK)") (class "Default")
      (node (ref "C35") (pin "2") (pinfunction "2_2") (pintype "passive"))
      (node (ref "U13") (pin "A15") (pinfunction "MIC1_P/DMIC1CLK_A15") (pintype "bidirectional"))
    )
    (net (code "77") (name "Net-(U13-MIC2_N{slash}DMIC2IN)") (class "Default")
      (node (ref "C38") (pin "2") (pinfunction "2_2") (pintype "passive"))
      (node (ref "U13") (pin "C15") (pinfunction "MIC2_N/DMIC2IN_C15") (pintype "bidirectional"))
    )
    (net (code "78") (name "Net-(U13-MIC2_P{slash}DMIC2CLK)") (class "Default")
      (node (ref "C37") (pin "2") (pinfunction "2_2") (pintype "passive"))
      (node (ref "U13") (pin "D16") (pinfunction "MIC2_P/DMIC2CLK_D16") (pintype "bidirectional"))
    )
    (net (code "79") (name "Net-(U13-VDDDIG)") (class "Default")
      (node (ref "C54") (pin "1") (pinfunction "1_1") (pintype "passive"))
      (node (ref "U13") (pin "D4") (pinfunction "VDDDIG_D4") (pintype "power_in"))
    )
    (net (code "80") (name "Net-(U13-VMID)") (class "Default")
      (node (ref "C76") (pin "1") (pinfunction "1_1") (pintype "passive"))
      (node (ref "U13") (pin "A9") (pinfunction "VMID_A9") (pintype "power_in"))
    )
    (net (code "81") (name "Net-(U13-VREF)") (class "Default")
      (node (ref "C78") (pin "1") (pinfunction "1_1") (pintype "passive"))
      (node (ref "U13") (pin "A11") (pinfunction "VREF_A11") (pintype "power_in"))
    )
    (net (code "82") (name "Net-(Z5-EN)") (class "Default")
      (node (ref "R33") (pin "2") (pinfunction "2_2") (pintype "passive"))
      (node (ref "Z5") (pin "1") (pinfunction "EN_1") (pintype "passive"))
    )
    (net (code "83") (name "unconnected-(U6-NC-PadE2)") (class "Default")
      (node (ref "U6") (pin "E2") (pinfunction "NC_E2") (pintype "passive"))
    )
    (net (code "84") (name "unconnected-(U7-LOAD-PadB1)") (class "Default")
      (node (ref "U7") (pin "B1") (pinfunction "LOAD_B1") (pintype "passive"))
    )
    (net (code "85") (name "unconnected-(X7-5-Pad9)") (class "Default")
      (node (ref "X7") (pin "9") (pinfunction "5_9") (pintype "passive"))
    )
    (net (code "86") (name "unconnected-(X7-6-Pad10)") (class "Default")
      (node (ref "X7") (pin "10") (pinfunction "6_10") (pintype "passive"))
    )
  )
)
